# shield.net
KiCad netlist of a schematic drawn in EAGLE
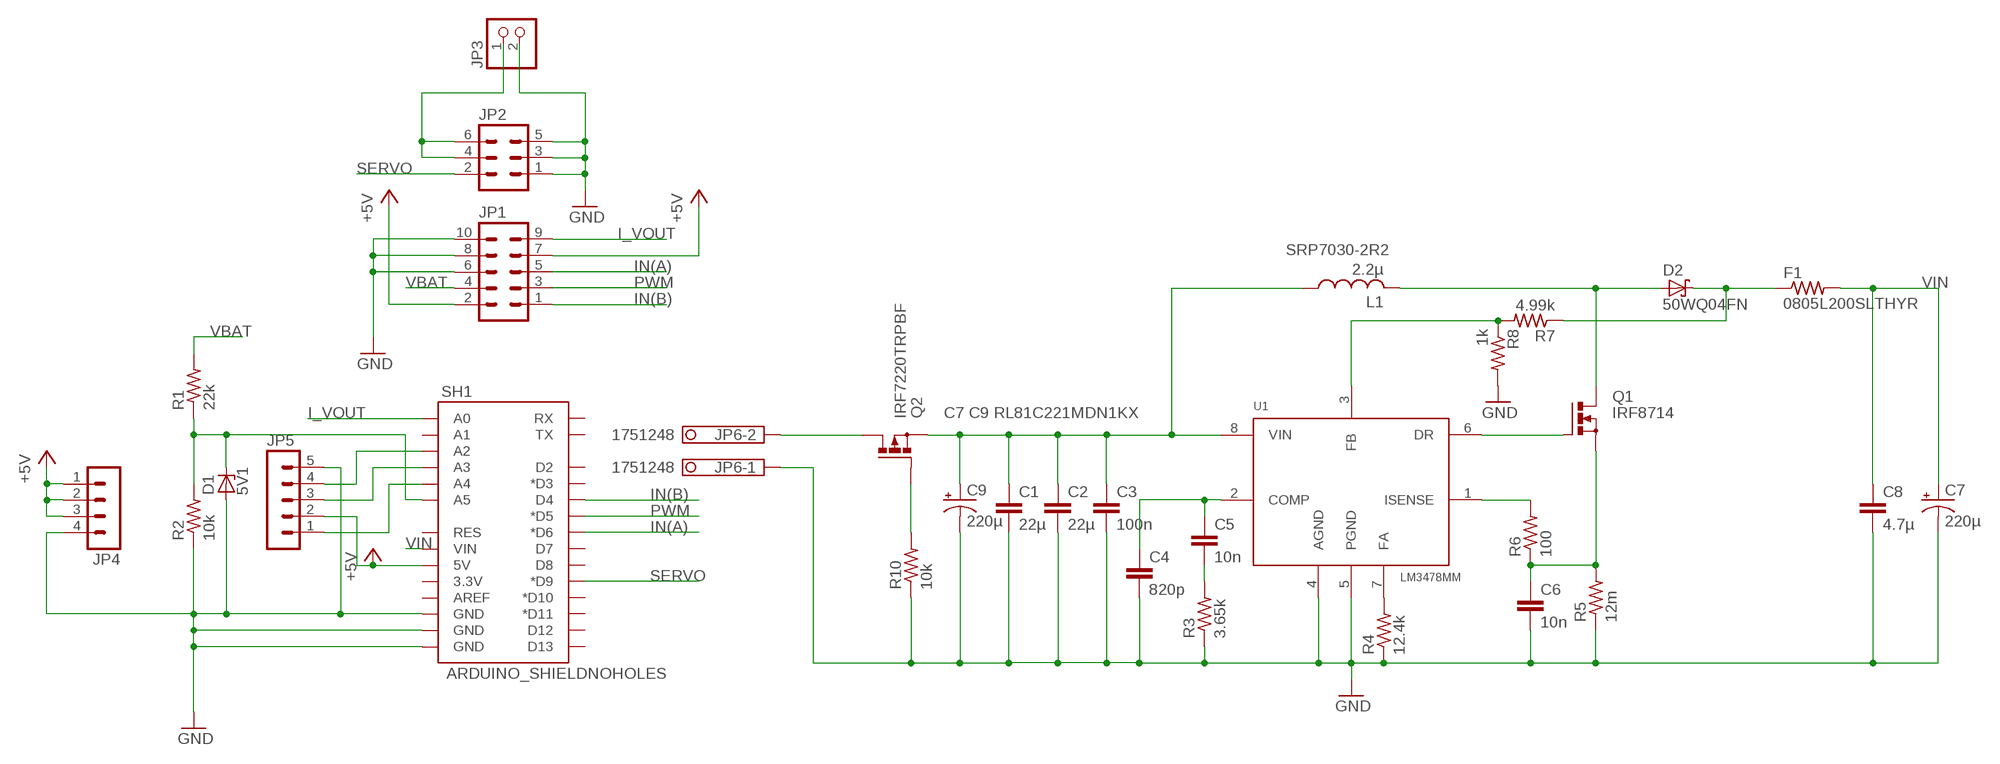
[diagram p0: schematic, sheet 1]

(export (version "E")
  (design (tool "Eeschema 10.0.6"))
  (components
    (comp (ref "C1")
      (value "22µ")
      (footprint "eagle-import:C3225")
      (libsource (lib "eagle-import") (part "C-EUC3225"))
    )
    (comp (ref "C2")
      (value "22µ")
      (footprint "eagle-import:C3225")
      (libsource (lib "eagle-import") (part "C-EUC3225"))
    )
    (comp (ref "C3")
      (value "100n")
      (footprint "eagle-import:C0805")
      (libsource (lib "eagle-import") (part "C-EUC0805"))
    )
    (comp (ref "C4")
      (value "820p")
      (footprint "eagle-import:C0805")
      (libsource (lib "eagle-import") (part "C-EUC0805"))
    )
    (comp (ref "C5")
      (value "10n")
      (footprint "eagle-import:C0805")
      (libsource (lib "eagle-import") (part "C-EUC0805"))
    )
    (comp (ref "C6")
      (value "10n")
      (footprint "eagle-import:C0805")
      (libsource (lib "eagle-import") (part "C-EUC0805"))
    )
    (comp (ref "C7")
      (value "220µ")
      (footprint "eagle-import:E3,5-8")
      (libsource (lib "eagle-import") (part "CPOL-USE3.5-8"))
    )
    (comp (ref "C8")
      (value "4.7µ")
      (footprint "eagle-import:C3225")
      (libsource (lib "eagle-import") (part "C-EUC3225"))
    )
    (comp (ref "C9")
      (value "220µ")
      (footprint "eagle-import:E3,5-8")
      (libsource (lib "eagle-import") (part "CPOL-USE3.5-8"))
    )
    (comp (ref "D1")
      (value "5V1")
      (footprint "eagle-import:SOT23")
      (libsource (lib "eagle-import") (part "ZENER-DIODESOT23"))
    )
    (comp (ref "D2")
      (value "50WQ04FN")
      (footprint "eagle-import:DPACK_1")
      (libsource (lib "eagle-import") (part "MBRD360T4G"))
    )
    (comp (ref "F1")
      (value "0805L200SLTHYR")
      (footprint "eagle-import:R0805")
      (libsource (lib "eagle-import") (part "R-US_R0805"))
    )
    (comp (ref "JP1")
      (value "ML10")
      (footprint "eagle-import:ML10")
      (libsource (lib "eagle-import") (part "ML10"))
    )
    (comp (ref "JP2")
      (value "ML6")
      (footprint "eagle-import:ML6")
      (libsource (lib "eagle-import") (part "ML6"))
    )
    (comp (ref "JP3")
      (value "PINHD-1X2")
      (footprint "eagle-import:1X02")
      (libsource (lib "eagle-import") (part "PINHD-1X2"))
    )
    (comp (ref "JP4")
      (value "MA04-1")
      (footprint "eagle-import:MA04-1")
      (libsource (lib "eagle-import") (part "MA04-1"))
    )
    (comp (ref "JP5")
      (value "MA05-1")
      (footprint "eagle-import:MA05-1")
      (fields (field (name "OC_FARNELL") "unknown") (field (name "OC_NEWARK") "unknown"))
      (libsource (lib "eagle-import") (part "MA05-1"))
    )
    (comp (ref "JP6")
      (value "1751248")
      (footprint "eagle-import:1751248")
      (libsource (lib "eagle-import") (part "1751248"))
    )
    (comp (ref "L1")
      (value "2.2µ")
      (footprint "eagle-import:SRP7030")
      (libsource (lib "eagle-import") (part "L-USSRP7030"))
    )
    (comp (ref "Q1")
      (value "IRF8714")
      (footprint "eagle-import:SO-08")
      (libsource (lib "eagle-import") (part "N-MOSFET-SO8S"))
    )
    (comp (ref "Q2")
      (value "IRF7220TRPBF")
      (footprint "eagle-import:SO-08")
      (libsource (lib "eagle-import") (part "P-MOSFET-SO8"))
    )
    (comp (ref "R1")
      (value "22k")
      (footprint "eagle-import:R0805")
      (libsource (lib "eagle-import") (part "R-US_R0805"))
    )
    (comp (ref "R2")
      (value "10k")
      (footprint "eagle-import:R0805")
      (libsource (lib "eagle-import") (part "R-US_R0805"))
    )
    (comp (ref "R3")
      (value "3.65k")
      (footprint "eagle-import:R0805")
      (libsource (lib "eagle-import") (part "R-US_R0805"))
    )
    (comp (ref "R4")
      (value "12.4k")
      (footprint "eagle-import:R0805")
      (libsource (lib "eagle-import") (part "R-US_R0805"))
    )
    (comp (ref "R5")
      (value "12m")
      (footprint "eagle-import:R1206")
      (libsource (lib "eagle-import") (part "R-US_R1206"))
    )
    (comp (ref "R6")
      (value "100")
      (footprint "eagle-import:R0805")
      (libsource (lib "eagle-import") (part "R-US_R0805"))
    )
    (comp (ref "R7")
      (value "4.99k")
      (footprint "eagle-import:R0805")
      (libsource (lib "eagle-import") (part "R-US_R0805"))
    )
    (comp (ref "R8")
      (value "1k")
      (footprint "eagle-import:R0805")
      (libsource (lib "eagle-import") (part "R-US_R0805"))
    )
    (comp (ref "R10")
      (value "10k")
      (footprint "eagle-import:R0805")
      (libsource (lib "eagle-import") (part "R-US_R0805"))
    )
    (comp (ref "SH1")
      (value "ARDUINO_SHIELDNOHOLES")
      (footprint "eagle-import:DUEMILANOVE_SHIELD_NOHOLES")
      (libsource (lib "eagle-import") (part "ARDUINO_SHIELDNOHOLES"))
    )
    (comp (ref "U1")
      (value "LM3478MM")
      (footprint "eagle-import:DGK_S-PDSO-G8")
      (libsource (lib "eagle-import") (part "LM3478MM"))
    )
  )
  (nets
    (net (code "1") (name "+5V") (class "Default")
      (node (ref "JP1") (pin "2") (pinfunction "2_2") (pintype "passive"))
      (node (ref "JP1") (pin "7") (pinfunction "7_7") (pintype "passive"))
      (node (ref "JP4") (pin "1") (pinfunction "1_1") (pintype "passive"))
      (node (ref "JP4") (pin "2") (pinfunction "2_2") (pintype "passive"))
      (node (ref "JP4") (pin "3") (pinfunction "3_3") (pintype "passive"))
      (node (ref "JP5") (pin "2") (pinfunction "2_2") (pintype "passive"))
      (node (ref "SH1") (pin "5V") (pinfunction "5V_5V") (pintype "bidirectional"))
    )
    (net (code "2") (name "/IN(A)") (class "Default")
      (node (ref "JP1") (pin "5") (pinfunction "5_5") (pintype "passive"))
      (node (ref "SH1") (pin "D6") (pinfunction "*D6_D6") (pintype "bidirectional"))
    )
    (net (code "3") (name "/IN(B)") (class "Default")
      (node (ref "JP1") (pin "1") (pinfunction "1_1") (pintype "passive"))
      (node (ref "SH1") (pin "D4") (pinfunction "D4_D4") (pintype "bidirectional"))
    )
    (net (code "4") (name "/I_VOUT") (class "Default")
      (node (ref "JP1") (pin "9") (pinfunction "9_9") (pintype "passive"))
      (node (ref "SH1") (pin "A0") (pinfunction "A0_A0") (pintype "bidirectional"))
    )
    (net (code "5") (name "/PWM") (class "Default")
      (node (ref "JP1") (pin "3") (pinfunction "3_3") (pintype "passive"))
      (node (ref "SH1") (pin "D5") (pinfunction "*D5_D5") (pintype "bidirectional"))
    )
    (net (code "6") (name "/SERVO") (class "Default")
      (node (ref "JP2") (pin "2") (pinfunction "2_2") (pintype "passive"))
      (node (ref "SH1") (pin "D9") (pinfunction "*D9_D9") (pintype "bidirectional"))
    )
    (net (code "7") (name "/VBAT") (class "Default")
      (node (ref "JP1") (pin "4") (pinfunction "4_4") (pintype "passive"))
      (node (ref "R1") (pin "2") (pinfunction "2_2") (pintype "passive"))
    )
    (net (code "8") (name "/VIN") (class "Default")
      (node (ref "C7") (pin "+") (pinfunction "+_+") (pintype "passive"))
      (node (ref "C8") (pin "1") (pinfunction "1_1") (pintype "passive"))
      (node (ref "F1") (pin "2") (pinfunction "2_2") (pintype "passive"))
      (node (ref "SH1") (pin "VIN") (pinfunction "VIN_VIN") (pintype "bidirectional"))
    )
    (net (code "9") (name "GND") (class "Default")
      (node (ref "C1") (pin "2") (pinfunction "2_2") (pintype "passive"))
      (node (ref "C2") (pin "2") (pinfunction "2_2") (pintype "passive"))
      (node (ref "C3") (pin "2") (pinfunction "2_2") (pintype "passive"))
      (node (ref "C4") (pin "2") (pinfunction "2_2") (pintype "passive"))
      (node (ref "C6") (pin "2") (pinfunction "2_2") (pintype "passive"))
      (node (ref "C7") (pin "-") (pinfunction "-_-") (pintype "passive"))
      (node (ref "C8") (pin "2") (pinfunction "2_2") (pintype "passive"))
      (node (ref "C9") (pin "-") (pinfunction "-_-") (pintype "passive"))
      (node (ref "D1") (pin "1") (pinfunction "A_1") (pintype "passive"))
      (node (ref "JP1") (pin "10") (pinfunction "10_10") (pintype "passive"))
      (node (ref "JP1") (pin "6") (pinfunction "6_6") (pintype "passive"))
      (node (ref "JP1") (pin "8") (pinfunction "8_8") (pintype "passive"))
      (node (ref "JP2") (pin "1") (pinfunction "1_1") (pintype "passive"))
      (node (ref "JP2") (pin "3") (pinfunction "3_3") (pintype "passive"))
      (node (ref "JP2") (pin "5") (pinfunction "5_5") (pintype "passive"))
      (node (ref "JP3") (pin "2") (pinfunction "2_2") (pintype "passive"))
      (node (ref "JP4") (pin "4") (pinfunction "4_4") (pintype "passive"))
      (node (ref "JP5") (pin "5") (pinfunction "5_5") (pintype "passive"))
      (node (ref "JP6") (pin "1") (pinfunction "K_1") (pintype "passive"))
      (node (ref "R10") (pin "1") (pinfunction "1_1") (pintype "passive"))
      (node (ref "R2") (pin "1") (pinfunction "1_1") (pintype "passive"))
      (node (ref "R3") (pin "1") (pinfunction "1_1") (pintype "passive"))
      (node (ref "R4") (pin "1") (pinfunction "1_1") (pintype "passive"))
      (node (ref "R5") (pin "1") (pinfunction "1_1") (pintype "passive"))
      (node (ref "R8") (pin "2") (pinfunction "2_2") (pintype "passive"))
      (node (ref "SH1") (pin "GND@0") (pinfunction "GND_GND@0") (pintype "bidirectional"))
      (node (ref "SH1") (pin "GND@1") (pinfunction "GND_GND@1") (pintype "bidirectional"))
      (node (ref "SH1") (pin "GND@2") (pinfunction "GND_GND@2") (pintype "bidirectional"))
      (node (ref "U1") (pin "4") (pinfunction "AGND_4") (pintype "bidirectional"))
      (node (ref "U1") (pin "5") (pinfunction "PGND_5") (pintype "bidirectional"))
    )
    (net (code "10") (name "Net-(C5-Pad2)") (class "Default")
      (node (ref "C5") (pin "2") (pinfunction "2_2") (pintype "passive"))
      (node (ref "R3") (pin "2") (pinfunction "2_2") (pintype "passive"))
    )
    (net (code "11") (name "Net-(C6-Pad1)") (class "Default")
      (node (ref "C6") (pin "1") (pinfunction "1_1") (pintype "passive"))
      (node (ref "Q1") (pin "1") (pinfunction "S_1") (pintype "passive"))
      (node (ref "Q1") (pin "2") (pinfunction "S_2") (pintype "passive"))
      (node (ref "Q1") (pin "3") (pinfunction "S_3") (pintype "passive"))
      (node (ref "R5") (pin "2") (pinfunction "2_2") (pintype "passive"))
      (node (ref "R6") (pin "1") (pinfunction "1_1") (pintype "passive"))
    )
    (net (code "12") (name "Net-(D1-C)") (class "Default")
      (node (ref "D1") (pin "3") (pinfunction "C_3") (pintype "passive"))
      (node (ref "R1") (pin "1") (pinfunction "1_1") (pintype "passive"))
      (node (ref "R2") (pin "2") (pinfunction "2_2") (pintype "passive"))
      (node (ref "SH1") (pin "A5") (pinfunction "A5_A5") (pintype "bidirectional"))
    )
    (net (code "13") (name "Net-(D2-A-PadA1)") (class "Default")
      (node (ref "D2") (pin "A1") (pinfunction "A_A1") (pintype "passive"))
      (node (ref "D2") (pin "A2") (pinfunction "A_A2") (pintype "passive"))
      (node (ref "L1") (pin "2") (pinfunction "2_2") (pintype "passive"))
      (node (ref "Q1") (pin "5") (pinfunction "D_5") (pintype "passive"))
      (node (ref "Q1") (pin "6") (pinfunction "D_6") (pintype "passive"))
      (node (ref "Q1") (pin "7") (pinfunction "D_7") (pintype "passive"))
      (node (ref "Q1") (pin "8") (pinfunction "D_8") (pintype "passive"))
    )
    (net (code "14") (name "Net-(D2-C)") (class "Default")
      (node (ref "D2") (pin "K") (pinfunction "C_K") (pintype "passive"))
      (node (ref "F1") (pin "1") (pinfunction "1_1") (pintype "passive"))
      (node (ref "R7") (pin "1") (pinfunction "1_1") (pintype "passive"))
    )
    (net (code "15") (name "Net-(JP2-Pad4)") (class "Default")
      (node (ref "JP2") (pin "4") (pinfunction "4_4") (pintype "passive"))
      (node (ref "JP2") (pin "6") (pinfunction "6_6") (pintype "passive"))
      (node (ref "JP3") (pin "1") (pinfunction "1_1") (pintype "passive"))
    )
    (net (code "16") (name "Net-(JP5-Pad1)") (class "Default")
      (node (ref "JP5") (pin "1") (pinfunction "1_1") (pintype "passive"))
      (node (ref "SH1") (pin "A4") (pinfunction "A4_A4") (pintype "bidirectional"))
    )
    (net (code "17") (name "Net-(JP5-Pad3)") (class "Default")
      (node (ref "JP5") (pin "3") (pinfunction "3_3") (pintype "passive"))
      (node (ref "SH1") (pin "A3") (pinfunction "A3_A3") (pintype "bidirectional"))
    )
    (net (code "18") (name "Net-(JP5-Pad4)") (class "Default")
      (node (ref "JP5") (pin "4") (pinfunction "4_4") (pintype "passive"))
      (node (ref "SH1") (pin "A2") (pinfunction "A2_A2") (pintype "bidirectional"))
    )
    (net (code "19") (name "Net-(JP6B-K)") (class "Default")
      (node (ref "JP6") (pin "2") (pinfunction "K_2") (pintype "passive"))
      (node (ref "Q2") (pin "5") (pinfunction "D_5") (pintype "passive"))
      (node (ref "Q2") (pin "6") (pinfunction "D_6") (pintype "passive"))
      (node (ref "Q2") (pin "7") (pinfunction "D_7") (pintype "passive"))
      (node (ref "Q2") (pin "8") (pinfunction "D_8") (pintype "passive"))
    )
    (net (code "20") (name "Net-(Q1-G)") (class "Default")
      (node (ref "Q1") (pin "4") (pinfunction "G_4") (pintype "passive"))
      (node (ref "U1") (pin "6") (pinfunction "DR_6") (pintype "bidirectional"))
    )
    (net (code "21") (name "Net-(Q2-G)") (class "Default")
      (node (ref "Q2") (pin "4") (pinfunction "G_4") (pintype "passive"))
      (node (ref "R10") (pin "2") (pinfunction "2_2") (pintype "passive"))
    )
    (net (code "22") (name "Net-(U1-COMP)") (class "Default")
      (node (ref "C4") (pin "1") (pinfunction "1_1") (pintype "passive"))
      (node (ref "C5") (pin "1") (pinfunction "1_1") (pintype "passive"))
      (node (ref "U1") (pin "2") (pinfunction "COMP_2") (pintype "bidirectional"))
    )
    (net (code "23") (name "Net-(U1-FA)") (class "Default")
      (node (ref "R4") (pin "2") (pinfunction "2_2") (pintype "passive"))
      (node (ref "U1") (pin "7") (pinfunction "FA_7") (pintype "bidirectional"))
    )
    (net (code "24") (name "Net-(U1-FB)") (class "Default")
      (node (ref "R7") (pin "2") (pinfunction "2_2") (pintype "passive"))
      (node (ref "R8") (pin "1") (pinfunction "1_1") (pintype "passive"))
      (node (ref "U1") (pin "3") (pinfunction "FB_3") (pintype "bidirectional"))
    )
    (net (code "25") (name "Net-(U1-ISENSE)") (class "Default")
      (node (ref "R6") (pin "2") (pinfunction "2_2") (pintype "passive"))
      (node (ref "U1") (pin "1") (pinfunction "ISENSE_1") (pintype "bidirectional"))
    )
    (net (code "26") (name "Net-(U1-VIN)") (class "Default")
      (node (ref "C1") (pin "1") (pinfunction "1_1") (pintype "passive"))
      (node (ref "C2") (pin "1") (pinfunction "1_1") (pintype "passive"))
      (node (ref "C3") (pin "1") (pinfunction "1_1") (pintype "passive"))
      (node (ref "C9") (pin "+") (pinfunction "+_+") (pintype "passive"))
      (node (ref "L1") (pin "1") (pinfunction "1_1") (pintype "passive"))
      (node (ref "Q2") (pin "1") (pinfunction "S_1") (pintype "passive"))
      (node (ref "Q2") (pin "2") (pinfunction "S_2") (pintype "passive"))
      (node (ref "Q2") (pin "3") (pinfunction "S_3") (pintype "passive"))
      (node (ref "U1") (pin "8") (pinfunction "VIN_8") (pintype "bidirectional"))
    )
    (net (code "27") (name "unconnected-(SH1-*D3-PadD3)") (class "Default")
      (node (ref "SH1") (pin "D3") (pinfunction "*D3_D3") (pintype "bidirectional"))
    )
    (net (code "28") (name "unconnected-(SH1-*D10-PadD10)") (class "Default")
      (node (ref "SH1") (pin "D10") (pinfunction "*D10_D10") (pintype "bidirectional"))
    )
    (net (code "29") (name "unconnected-(SH1-*D11-PadD11)") (class "Default")
      (node (ref "SH1") (pin "D11") (pinfunction "*D11_D11") (pintype "bidirectional"))
    )
    (net (code "30") (name "unconnected-(SH1-Pad3.3V)") (class "Default")
      (node (ref "SH1") (pin "3.3V") (pinfunction "3.3V_3.3V") (pintype "bidirectional"))
    )
    (net (code "31") (name "unconnected-(SH1-PadA1)") (class "Default")
      (node (ref "SH1") (pin "A1") (pinfunction "A1_A1") (pintype "bidirectional"))
    )
    (net (code "32") (name "unconnected-(SH1-PadAREF)") (class "Default")
      (node (ref "SH1") (pin "AREF") (pinfunction "AREF_AREF") (pintype "bidirectional"))
    )
    (net (code "33") (name "unconnected-(SH1-PadD2)") (class "Default")
      (node (ref "SH1") (pin "D2") (pinfunction "D2_D2") (pintype "bidirectional"))
    )
    (net (code "34") (name "unconnected-(SH1-PadD7)") (class "Default")
      (node (ref "SH1") (pin "D7") (pinfunction "D7_D7") (pintype "bidirectional"))
    )
    (net (code "35") (name "unconnected-(SH1-PadD8)") (class "Default")
      (node (ref "SH1") (pin "D8") (pinfunction "D8_D8") (pintype "bidirectional"))
    )
    (net (code "36") (name "unconnected-(SH1-PadD12)") (class "Default")
      (node (ref "SH1") (pin "D12") (pinfunction "D12_D12") (pintype "bidirectional"))
    )
    (net (code "37") (name "unconnected-(SH1-PadD13)") (class "Default")
      (node (ref "SH1") (pin "D13") (pinfunction "D13_D13") (pintype "bidirectional"))
    )
    (net (code "38") (name "unconnected-(SH1-PadRES)") (class "Default")
      (node (ref "SH1") (pin "RES") (pinfunction "RES_RES") (pintype "bidirectional"))
    )
    (net (code "39") (name "unconnected-(SH1-PadRX)") (class "Default")
      (node (ref "SH1") (pin "RX") (pinfunction "RX_RX") (pintype "bidirectional"))
    )
    (net (code "40") (name "unconnected-(SH1-PadTX)") (class "Default")
      (node (ref "SH1") (pin "TX") (pinfunction "TX_TX") (pintype "bidirectional"))
    )
  )
)
